# schSensorChassiNano.net
KiCad netlist of a schematic drawn in Altium Designer
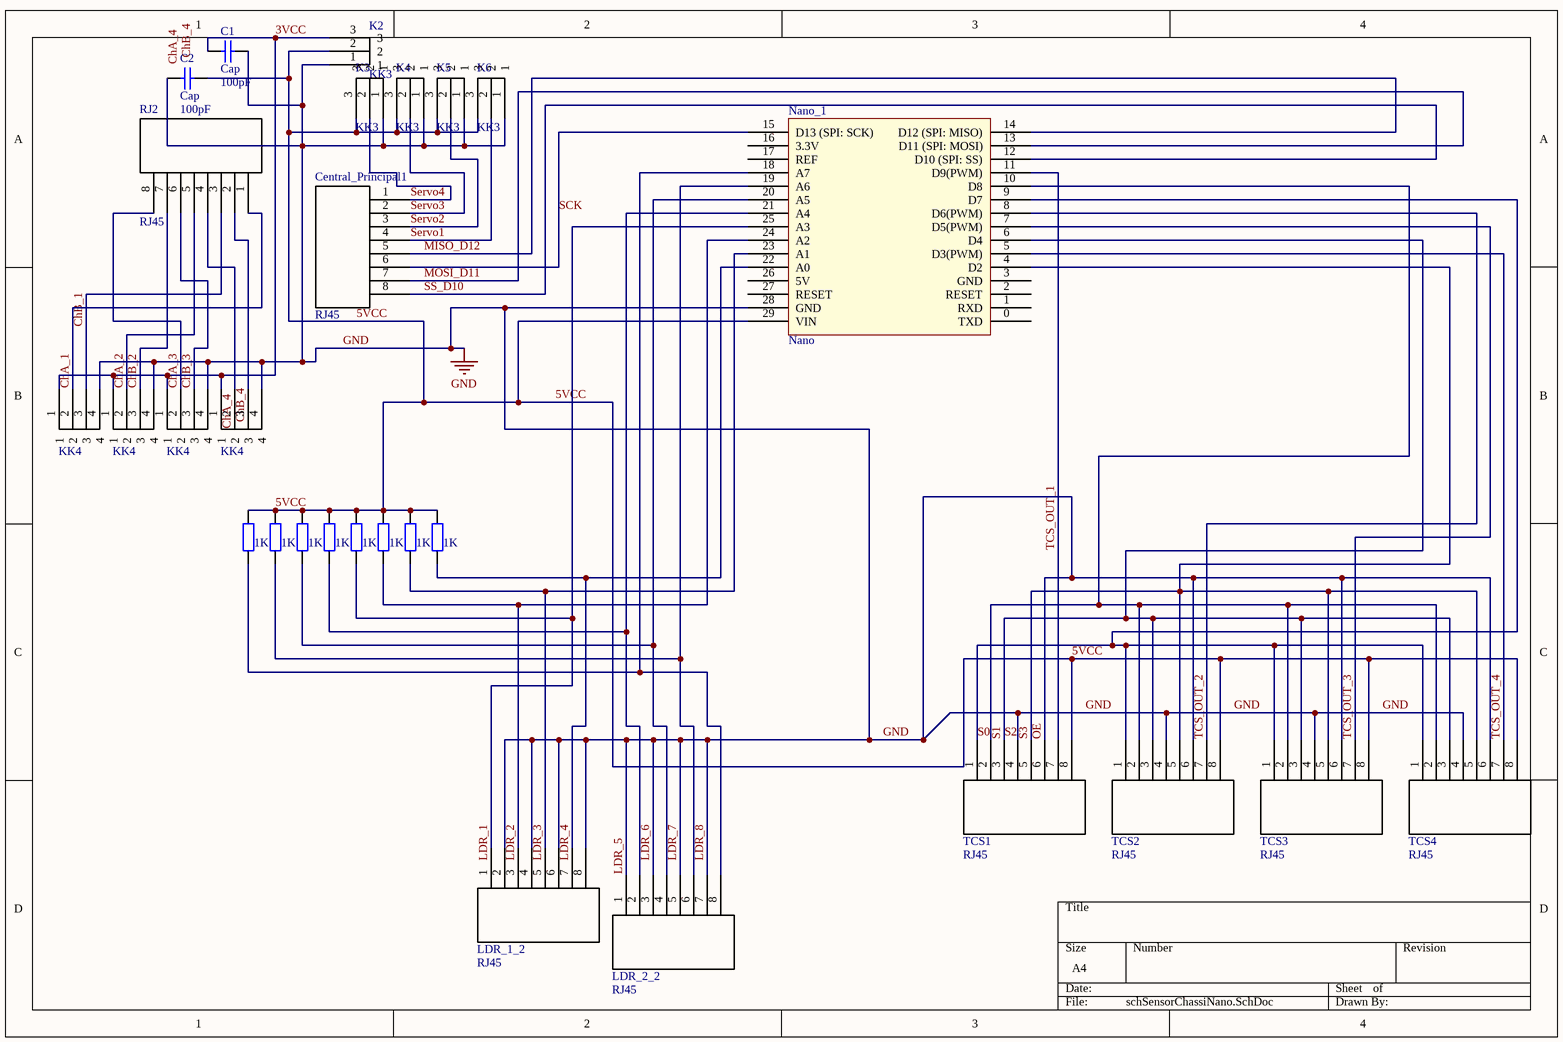
[diagram p0: schSensorChassiNano.SchDoc]

(export (version "E")
  (design (tool "Eeschema 10.0.6"))
  (components
    (comp (ref "C1")
      (value "Cap")
      (footprint "RAD-0.3")
      (description "Capacitor")
      (fields (field (name "ALTIUM_VALUE") "100pF") (field (name "PUBLISHER") "Altium Limited"))
      (libsource (lib "Miscellaneous Devices") (part "Cap"))
    )
    (comp (ref "C2")
      (value "Cap")
      (footprint "RAD-0.3")
      (description "Capacitor")
      (fields (field (name "ALTIUM_VALUE") "100pF") (field (name "PUBLISHER") "Altium Limited"))
      (libsource (lib "Miscellaneous Devices") (part "Cap"))
    )
    (comp (ref "Central_Principal1")
      (value "RJ45")
      (footprint "RJ45_90")
      (libsource (lib "Componentes_Open") (part "RJ45"))
    )
    (comp (ref "Encoder_4")
      (value "KK4")
      (footprint "4-vias")
      (libsource (lib "Componentes_Open") (part "KK4Vias"))
    )
    (comp (ref "Encoder_5")
      (value "KK4")
      (footprint "4-vias")
      (libsource (lib "Componentes_Open") (part "KK4Vias"))
    )
    (comp (ref "Encoder_6")
      (value "KK4")
      (footprint "4-vias")
      (libsource (lib "Componentes_Open") (part "KK4Vias"))
    )
    (comp (ref "K1") (value "KK4") (footprint "4-vias") (libsource (lib "Componentes_Open") (part "KK4Vias")))
    (comp (ref "K2") (value "KK3") (footprint "3-vias") (libsource (lib "Componentes_Open") (part "KK3Vias")))
    (comp (ref "K3") (value "KK3") (footprint "3-vias") (libsource (lib "Componentes_Open") (part "KK3Vias")))
    (comp (ref "K4") (value "KK3") (footprint "3-vias") (libsource (lib "Componentes_Open") (part "KK3Vias")))
    (comp (ref "K5") (value "KK3") (footprint "3-vias") (libsource (lib "Componentes_Open") (part "KK3Vias")))
    (comp (ref "K6") (value "KK3") (footprint "3-vias") (libsource (lib "Componentes_Open") (part "KK3Vias")))
    (comp (ref "LDR_1_2")
      (value "RJ45")
      (footprint "RJ45_90")
      (libsource (lib "Componentes_Open") (part "RJ45"))
    )
    (comp (ref "LDR_2_2")
      (value "RJ45")
      (footprint "RJ45_90")
      (libsource (lib "Componentes_Open") (part "RJ45"))
    )
    (comp (ref "Nano_1")
      (value "Nano")
      (footprint "Arduino_Nano")
      (libsource (lib "Componentes_Open") (part "Arduino_Nano"))
    )
    (comp (ref "R17")
      (value "1K")
      (footprint "AXIAL-0.4")
      (description "Resistor")
      (fields (field (name "Comment") "Res2") (field (name "PUBLISHER") "Altium Limited"))
      (libsource (lib "Miscellaneous Devices") (part "Res2"))
    )
    (comp (ref "R18")
      (value "1K")
      (footprint "AXIAL-0.4")
      (description "Resistor")
      (fields (field (name "Comment") "Res2") (field (name "PUBLISHER") "Altium Limited"))
      (libsource (lib "Miscellaneous Devices") (part "Res2"))
    )
    (comp (ref "R19")
      (value "1K")
      (footprint "AXIAL-0.4")
      (description "Resistor")
      (fields (field (name "Comment") "Res2") (field (name "PUBLISHER") "Altium Limited"))
      (libsource (lib "Miscellaneous Devices") (part "Res2"))
    )
    (comp (ref "R20")
      (value "1K")
      (footprint "AXIAL-0.4")
      (description "Resistor")
      (fields (field (name "Comment") "Res2") (field (name "PUBLISHER") "Altium Limited"))
      (libsource (lib "Miscellaneous Devices") (part "Res2"))
    )
    (comp (ref "R21")
      (value "1K")
      (footprint "AXIAL-0.4")
      (description "Resistor")
      (fields (field (name "Comment") "Res2") (field (name "PUBLISHER") "Altium Limited"))
      (libsource (lib "Miscellaneous Devices") (part "Res2"))
    )
    (comp (ref "R22")
      (value "1K")
      (footprint "AXIAL-0.4")
      (description "Resistor")
      (fields (field (name "Comment") "Res2") (field (name "PUBLISHER") "Altium Limited"))
      (libsource (lib "Miscellaneous Devices") (part "Res2"))
    )
    (comp (ref "R23")
      (value "1K")
      (footprint "AXIAL-0.4")
      (description "Resistor")
      (fields (field (name "Comment") "Res2") (field (name "PUBLISHER") "Altium Limited"))
      (libsource (lib "Miscellaneous Devices") (part "Res2"))
    )
    (comp (ref "R24")
      (value "1K")
      (footprint "AXIAL-0.4")
      (description "Resistor")
      (fields (field (name "Comment") "Res2") (field (name "PUBLISHER") "Altium Limited"))
      (libsource (lib "Miscellaneous Devices") (part "Res2"))
    )
    (comp (ref "RJ2") (value "RJ45") (footprint "RJ45_90") (libsource (lib "Componentes_Open") (part "RJ45")))
    (comp (ref "TCS1")
      (value "RJ45")
      (footprint "RJ45_90")
      (libsource (lib "Componentes_Open") (part "RJ45"))
    )
    (comp (ref "TCS2")
      (value "RJ45")
      (footprint "RJ45_90")
      (libsource (lib "Componentes_Open") (part "RJ45"))
    )
    (comp (ref "TCS3")
      (value "RJ45")
      (footprint "RJ45_90")
      (libsource (lib "Componentes_Open") (part "RJ45"))
    )
    (comp (ref "TCS4")
      (value "RJ45")
      (footprint "RJ45_90")
      (libsource (lib "Componentes_Open") (part "RJ45"))
    )
  )
  (nets
    (net (code "1") (name "/3VCC") (class "Default")
      (node (ref "C1") (pin "1") (pinfunction "1_1") (pintype "passive"))
      (node (ref "Encoder_4") (pin "1") (pinfunction "1_1") (pintype "passive"))
      (node (ref "Encoder_5") (pin "1") (pinfunction "1_1") (pintype "passive"))
      (node (ref "Encoder_6") (pin "1") (pinfunction "1_1") (pintype "passive"))
      (node (ref "K1") (pin "1") (pinfunction "1_1") (pintype "passive"))
      (node (ref "K2") (pin "3") (pinfunction "3_3") (pintype "passive"))
    )
    (net (code "2") (name "/5VCC") (class "Default")
      (node (ref "C2") (pin "2") (pinfunction "2_2") (pintype "passive"))
      (node (ref "K2") (pin "2") (pinfunction "2_2") (pintype "passive"))
      (node (ref "K3") (pin "3") (pinfunction "3_3") (pintype "passive"))
      (node (ref "K4") (pin "3") (pinfunction "3_3") (pintype "passive"))
      (node (ref "K5") (pin "3") (pinfunction "3_3") (pintype "passive"))
      (node (ref "K6") (pin "3") (pinfunction "3_3") (pintype "passive"))
      (node (ref "Nano_1") (pin "29") (pinfunction "VIN_29") (pintype "passive"))
      (node (ref "R17") (pin "2") (pinfunction "2_2") (pintype "passive"))
      (node (ref "R18") (pin "2") (pinfunction "2_2") (pintype "passive"))
      (node (ref "R19") (pin "2") (pinfunction "2_2") (pintype "passive"))
      (node (ref "R20") (pin "2") (pinfunction "2_2") (pintype "passive"))
      (node (ref "R21") (pin "2") (pinfunction "2_2") (pintype "passive"))
      (node (ref "R22") (pin "2") (pinfunction "2_2") (pintype "passive"))
      (node (ref "R23") (pin "2") (pinfunction "2_2") (pintype "passive"))
      (node (ref "R24") (pin "2") (pinfunction "2_2") (pintype "passive"))
      (node (ref "TCS1") (pin "8") (pinfunction "8_8") (pintype "passive"))
      (node (ref "TCS2") (pin "8") (pinfunction "8_8") (pintype "passive"))
      (node (ref "TCS3") (pin "8") (pinfunction "8_8") (pintype "passive"))
      (node (ref "TCS4") (pin "8") (pinfunction "8_8") (pintype "passive"))
    )
    (net (code "3") (name "/ChA_1") (class "Default")
      (node (ref "K1") (pin "2") (pinfunction "2_2") (pintype "passive"))
      (node (ref "RJ2") (pin "1") (pinfunction "9_1") (pintype "passive"))
    )
    (net (code "4") (name "/ChA_2") (class "Default")
      (node (ref "Encoder_4") (pin "2") (pinfunction "2_2") (pintype "passive"))
      (node (ref "RJ2") (pin "5") (pinfunction "5_5") (pintype "passive"))
    )
    (net (code "5") (name "/ChA_3") (class "Default")
      (node (ref "Encoder_5") (pin "2") (pinfunction "2_2") (pintype "passive"))
      (node (ref "RJ2") (pin "8") (pinfunction "8_8") (pintype "passive"))
    )
    (net (code "7") (name "/ChB_1") (class "Default")
      (node (ref "K1") (pin "3") (pinfunction "3_3") (pintype "passive"))
      (node (ref "RJ2") (pin "3") (pinfunction "3_3") (pintype "passive"))
    )
    (net (code "8") (name "/ChB_2") (class "Default")
      (node (ref "Encoder_4") (pin "3") (pinfunction "3_3") (pintype "passive"))
      (node (ref "RJ2") (pin "7") (pinfunction "7_7") (pintype "passive"))
    )
    (net (code "9") (name "/ChB_3") (class "Default")
      (node (ref "Encoder_5") (pin "3") (pinfunction "3_3") (pintype "passive"))
      (node (ref "RJ2") (pin "6") (pinfunction "6_6") (pintype "passive"))
    )
    (net (code "15") (name "/MISO_D12") (class "Default")
      (node (ref "Central_Principal1") (pin "5") (pinfunction "5_5") (pintype "passive"))
      (node (ref "Nano_1") (pin "14") (pinfunction "D12_(SPI:_MISO)_14") (pintype "passive"))
    )
    (net (code "16") (name "/MOSI_D11") (class "Default")
      (node (ref "Central_Principal1") (pin "7") (pinfunction "7_7") (pintype "passive"))
      (node (ref "Nano_1") (pin "13") (pinfunction "D11_(SPI:_MOSI)_13") (pintype "passive"))
    )
    (net (code "17") (name "/S0") (class "Default")
      (node (ref "Nano_1") (pin "9") (pinfunction "D7_9") (pintype "passive"))
      (node (ref "TCS1") (pin "1") (pinfunction "9_1") (pintype "passive"))
      (node (ref "TCS2") (pin "1") (pinfunction "9_1") (pintype "passive"))
      (node (ref "TCS3") (pin "1") (pinfunction "9_1") (pintype "passive"))
      (node (ref "TCS4") (pin "1") (pinfunction "9_1") (pintype "passive"))
    )
    (net (code "18") (name "/S1") (class "Default")
      (node (ref "Nano_1") (pin "6") (pinfunction "D4_6") (pintype "passive"))
      (node (ref "TCS1") (pin "3") (pinfunction "3_3") (pintype "passive"))
      (node (ref "TCS2") (pin "3") (pinfunction "3_3") (pintype "passive"))
      (node (ref "TCS3") (pin "3") (pinfunction "3_3") (pintype "passive"))
      (node (ref "TCS4") (pin "3") (pinfunction "3_3") (pintype "passive"))
    )
    (net (code "19") (name "/S3") (class "Default")
      (node (ref "Nano_1") (pin "4") (pinfunction "D2_4") (pintype "passive"))
      (node (ref "TCS1") (pin "5") (pinfunction "5_5") (pintype "passive"))
      (node (ref "TCS2") (pin "5") (pinfunction "5_5") (pintype "passive"))
      (node (ref "TCS3") (pin "5") (pinfunction "5_5") (pintype "passive"))
      (node (ref "TCS4") (pin "5") (pinfunction "5_5") (pintype "passive"))
    )
    (net (code "20") (name "/SCK") (class "Default")
      (node (ref "Central_Principal1") (pin "6") (pinfunction "6_6") (pintype "passive"))
      (node (ref "Nano_1") (pin "15") (pinfunction "D13_(SPI:_SCK)_15") (pintype "passive"))
    )
    (net (code "21") (name "/SS_D10") (class "Default")
      (node (ref "Central_Principal1") (pin "8") (pinfunction "8_8") (pintype "passive"))
      (node (ref "Nano_1") (pin "12") (pinfunction "D10_(SPI:_SS)_12") (pintype "passive"))
    )
    (net (code "22") (name "/Servo1") (class "Default")
      (node (ref "Central_Principal1") (pin "4") (pinfunction "4_4") (pintype "passive"))
      (node (ref "K6") (pin "2") (pinfunction "2_2") (pintype "passive"))
    )
    (net (code "23") (name "/Servo2") (class "Default")
      (node (ref "Central_Principal1") (pin "3") (pinfunction "3_3") (pintype "passive"))
      (node (ref "K5") (pin "2") (pinfunction "2_2") (pintype "passive"))
    )
    (net (code "24") (name "/Servo3") (class "Default")
      (node (ref "Central_Principal1") (pin "2") (pinfunction "2_2") (pintype "passive"))
      (node (ref "K4") (pin "2") (pinfunction "2_2") (pintype "passive"))
    )
    (net (code "25") (name "/Servo4") (class "Default")
      (node (ref "Central_Principal1") (pin "1") (pinfunction "9_1") (pintype "passive"))
      (node (ref "K3") (pin "2") (pinfunction "2_2") (pintype "passive"))
    )
    (net (code "26") (name "/TCS_OUT_1") (class "Default")
      (node (ref "Nano_1") (pin "11") (pinfunction "D9(PWM)_11") (pintype "passive"))
      (node (ref "TCS1") (pin "7") (pinfunction "7_7") (pintype "passive"))
    )
    (net (code "27") (name "/TCS_OUT_2") (class "Default")
      (node (ref "Nano_1") (pin "8") (pinfunction "D6(PWM)_8") (pintype "passive"))
      (node (ref "TCS2") (pin "7") (pinfunction "7_7") (pintype "passive"))
    )
    (net (code "28") (name "/TCS_OUT_3") (class "Default")
      (node (ref "Nano_1") (pin "7") (pinfunction "D5(PWM)_7") (pintype "passive"))
      (node (ref "TCS3") (pin "7") (pinfunction "7_7") (pintype "passive"))
    )
    (net (code "29") (name "/TCS_OUT_4") (class "Default")
      (node (ref "Nano_1") (pin "5") (pinfunction "D3(PWM)_5") (pintype "passive"))
      (node (ref "TCS4") (pin "7") (pinfunction "7_7") (pintype "passive"))
    )
    (net (code "30") (name "GND") (class "Default")
      (node (ref "C1") (pin "2") (pinfunction "2_2") (pintype "passive"))
      (node (ref "C2") (pin "1") (pinfunction "1_1") (pintype "passive"))
      (node (ref "Encoder_4") (pin "4") (pinfunction "4_4") (pintype "passive"))
      (node (ref "Encoder_5") (pin "4") (pinfunction "4_4") (pintype "passive"))
      (node (ref "Encoder_6") (pin "4") (pinfunction "4_4") (pintype "passive"))
      (node (ref "K1") (pin "4") (pinfunction "4_4") (pintype "passive"))
      (node (ref "K2") (pin "1") (pinfunction "1_1") (pintype "passive"))
      (node (ref "K3") (pin "1") (pinfunction "1_1") (pintype "passive"))
      (node (ref "K4") (pin "1") (pinfunction "1_1") (pintype "passive"))
      (node (ref "K5") (pin "1") (pinfunction "1_1") (pintype "passive"))
      (node (ref "K6") (pin "1") (pinfunction "1_1") (pintype "passive"))
      (node (ref "LDR_1_2") (pin "2") (pinfunction "2_2") (pintype "passive"))
      (node (ref "LDR_1_2") (pin "4") (pinfunction "4_4") (pintype "passive"))
      (node (ref "LDR_1_2") (pin "6") (pinfunction "6_6") (pintype "passive"))
      (node (ref "LDR_1_2") (pin "8") (pinfunction "8_8") (pintype "passive"))
      (node (ref "LDR_2_2") (pin "1") (pinfunction "9_1") (pintype "passive"))
      (node (ref "LDR_2_2") (pin "3") (pinfunction "3_3") (pintype "passive"))
      (node (ref "LDR_2_2") (pin "5") (pinfunction "5_5") (pintype "passive"))
      (node (ref "LDR_2_2") (pin "7") (pinfunction "7_7") (pintype "passive"))
      (node (ref "Nano_1") (pin "28") (pinfunction "GND_28") (pintype "passive"))
      (node (ref "TCS1") (pin "4") (pinfunction "4_4") (pintype "passive"))
      (node (ref "TCS1") (pin "6") (pinfunction "6_6") (pintype "passive"))
      (node (ref "TCS2") (pin "4") (pinfunction "4_4") (pintype "passive"))
      (node (ref "TCS2") (pin "6") (pinfunction "6_6") (pintype "passive"))
      (node (ref "TCS3") (pin "4") (pinfunction "4_4") (pintype "passive"))
      (node (ref "TCS3") (pin "6") (pinfunction "6_6") (pintype "passive"))
      (node (ref "TCS4") (pin "4") (pinfunction "4_4") (pintype "passive"))
      (node (ref "TCS4") (pin "6") (pinfunction "6_6") (pintype "passive"))
    )
    (net (code "31") (name "Net-(Encoder_6-Pad2)") (class "Default")
      (node (ref "Encoder_6") (pin "2") (pinfunction "2_2") (pintype "passive"))
      (node (ref "RJ2") (pin "4") (pinfunction "4_4") (pintype "passive"))
    )
    (net (code "32") (name "Net-(Encoder_6-Pad3)") (class "Default")
      (node (ref "Encoder_6") (pin "3") (pinfunction "3_3") (pintype "passive"))
      (node (ref "RJ2") (pin "2") (pinfunction "2_2") (pintype "passive"))
    )
    (net (code "33") (name "Net-(LDR_1_2-9)") (class "Default")
      (node (ref "LDR_1_2") (pin "1") (pinfunction "9_1") (pintype "passive"))
      (node (ref "Nano_1") (pin "25") (pinfunction "A3_25") (pintype "passive"))
      (node (ref "R21") (pin "1") (pinfunction "1_1") (pintype "passive"))
    )
    (net (code "34") (name "Net-(Nano_1-A0)") (class "Default")
      (node (ref "LDR_1_2") (pin "7") (pinfunction "7_7") (pintype "passive"))
      (node (ref "Nano_1") (pin "22") (pinfunction "A0_22") (pintype "passive"))
      (node (ref "R24") (pin "1") (pinfunction "1_1") (pintype "passive"))
    )
    (net (code "35") (name "Net-(Nano_1-A1)") (class "Default")
      (node (ref "LDR_1_2") (pin "5") (pinfunction "5_5") (pintype "passive"))
      (node (ref "Nano_1") (pin "23") (pinfunction "A1_23") (pintype "passive"))
      (node (ref "R23") (pin "1") (pinfunction "1_1") (pintype "passive"))
    )
    (net (code "36") (name "Net-(Nano_1-A2)") (class "Default")
      (node (ref "LDR_1_2") (pin "3") (pinfunction "3_3") (pintype "passive"))
      (node (ref "Nano_1") (pin "24") (pinfunction "A2_24") (pintype "passive"))
      (node (ref "R22") (pin "1") (pinfunction "1_1") (pintype "passive"))
    )
    (net (code "37") (name "Net-(Nano_1-A4)") (class "Default")
      (node (ref "LDR_2_2") (pin "2") (pinfunction "2_2") (pintype "passive"))
      (node (ref "Nano_1") (pin "21") (pinfunction "A4_21") (pintype "passive"))
      (node (ref "R20") (pin "1") (pinfunction "1_1") (pintype "passive"))
    )
    (net (code "38") (name "Net-(Nano_1-A5)") (class "Default")
      (node (ref "LDR_2_2") (pin "4") (pinfunction "4_4") (pintype "passive"))
      (node (ref "Nano_1") (pin "20") (pinfunction "A5_20") (pintype "passive"))
      (node (ref "R19") (pin "1") (pinfunction "1_1") (pintype "passive"))
    )
    (net (code "39") (name "Net-(Nano_1-A6)") (class "Default")
      (node (ref "LDR_2_2") (pin "6") (pinfunction "6_6") (pintype "passive"))
      (node (ref "Nano_1") (pin "19") (pinfunction "A6_19") (pintype "passive"))
      (node (ref "R18") (pin "1") (pinfunction "1_1") (pintype "passive"))
    )
    (net (code "40") (name "Net-(Nano_1-A7)") (class "Default")
      (node (ref "LDR_2_2") (pin "8") (pinfunction "8_8") (pintype "passive"))
      (node (ref "Nano_1") (pin "18") (pinfunction "A7_18") (pintype "passive"))
      (node (ref "R17") (pin "1") (pinfunction "1_1") (pintype "passive"))
    )
    (net (code "41") (name "Net-(Nano_1-D8)") (class "Default")
      (node (ref "Nano_1") (pin "10") (pinfunction "D8_10") (pintype "passive"))
      (node (ref "TCS1") (pin "2") (pinfunction "2_2") (pintype "passive"))
      (node (ref "TCS2") (pin "2") (pinfunction "2_2") (pintype "passive"))
      (node (ref "TCS3") (pin "2") (pinfunction "2_2") (pintype "passive"))
      (node (ref "TCS4") (pin "2") (pinfunction "2_2") (pintype "passive"))
    )
    (net (code "42") (name "unconnected-(Nano_1-3.3V-Pad16)") (class "Default")
      (node (ref "Nano_1") (pin "16") (pinfunction "3.3V_16") (pintype "passive"))
    )
    (net (code "43") (name "unconnected-(Nano_1-5V-Pad26)") (class "Default")
      (node (ref "Nano_1") (pin "26") (pinfunction "5V_26") (pintype "passive"))
    )
    (net (code "44") (name "unconnected-(Nano_1-GND-Pad3)") (class "Default")
      (node (ref "Nano_1") (pin "3") (pinfunction "GND_3") (pintype "passive"))
    )
    (net (code "45") (name "unconnected-(Nano_1-REF-Pad17)") (class "Default")
      (node (ref "Nano_1") (pin "17") (pinfunction "REF_17") (pintype "passive"))
    )
    (net (code "46") (name "unconnected-(Nano_1-RESET-Pad2)") (class "Default")
      (node (ref "Nano_1") (pin "2") (pinfunction "RESET_2") (pintype "passive"))
    )
    (net (code "47") (name "unconnected-(Nano_1-RESET-Pad27)") (class "Default")
      (node (ref "Nano_1") (pin "27") (pinfunction "RESET_27") (pintype "passive"))
    )
    (net (code "48") (name "unconnected-(Nano_1-RXD-Pad1)") (class "Default")
      (node (ref "Nano_1") (pin "1") (pinfunction "RXD_1") (pintype "passive"))
    )
    (net (code "49") (name "unconnected-(Nano_1-TXD-Pad0)") (class "Default")
      (node (ref "Nano_1") (pin "0") (pinfunction "TXD_0") (pintype "passive"))
    )
  )
)
